# Proiect_v67.net
KiCad netlist of a schematic drawn in EAGLE
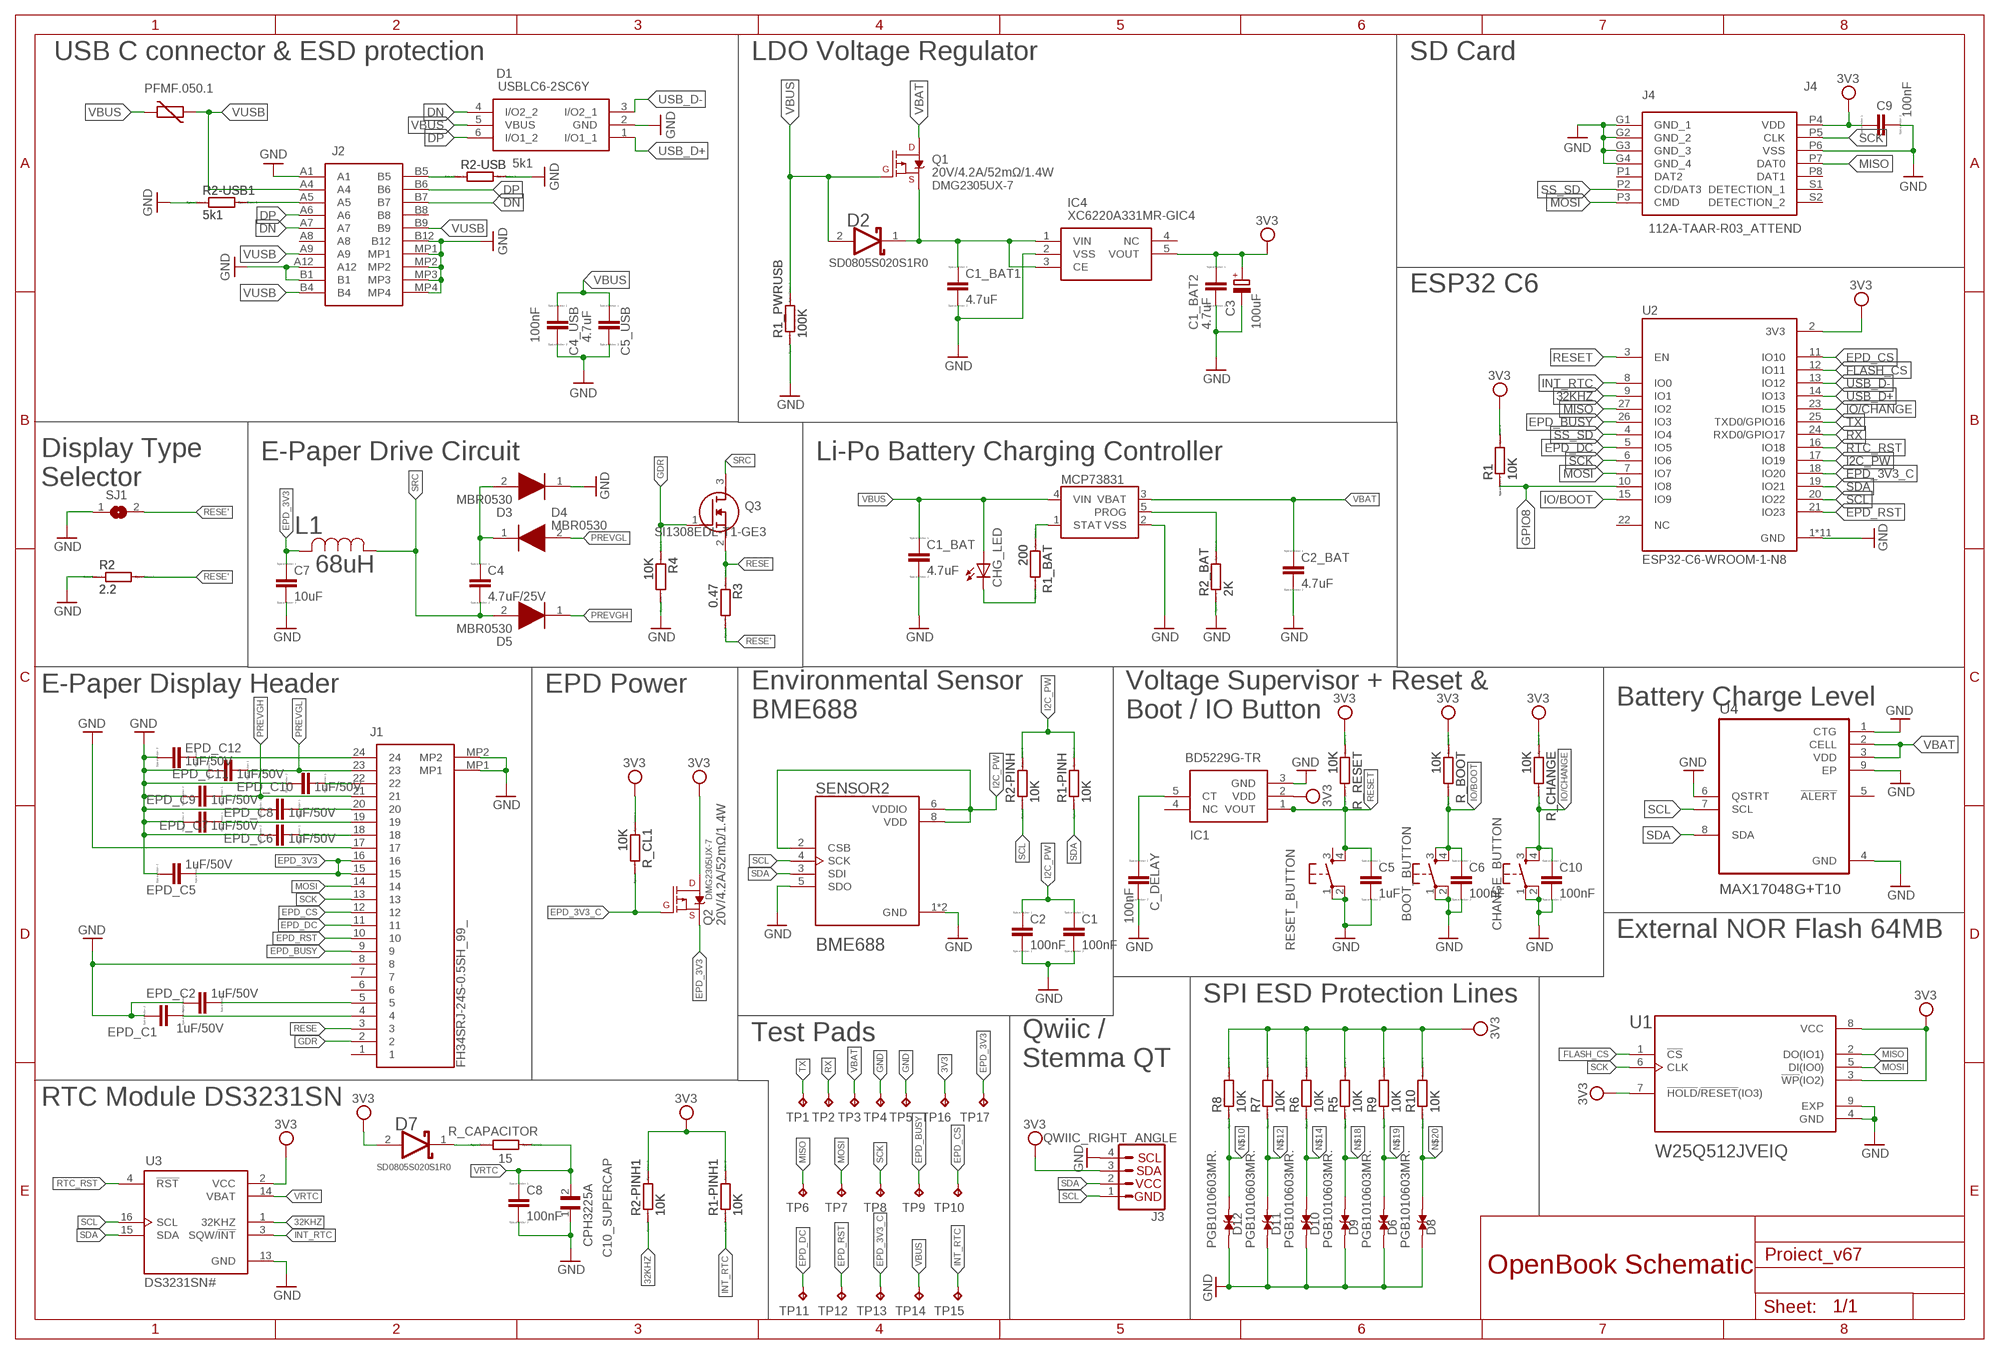
[diagram p0: schematic, sheet 1]

(export (version "E")
  (design (tool "Eeschema 10.0.6"))
  (components
    (comp (ref "BOOT_BUTTON")
      (value "BUTTON_CUSYOMV1.")
      (footprint "eagle-import:MYBUTTON")
      (libsource (lib "eagle-import") (part "BUTTON_CUSYOMV1."))
    )
    (comp (ref "C1")
      (value "100nF")
      (footprint "eagle-import:EAGLE-LTSPICE_C0402")
      (libsource (lib "eagle-import") (part "EAGLE-LTSPICE_C"))
    )
    (comp (ref "C1_BAT")
      (value "4.7uF")
      (footprint "eagle-import:EAGLE-LTSPICE_C0402")
      (libsource (lib "eagle-import") (part "EAGLE-LTSPICE_C"))
    )
    (comp (ref "C1_BAT1")
      (value "4.7uF")
      (footprint "eagle-import:EAGLE-LTSPICE_C0402")
      (libsource (lib "eagle-import") (part "EAGLE-LTSPICE_C"))
    )
    (comp (ref "C1_BAT2")
      (value "4.7uF")
      (footprint "eagle-import:EAGLE-LTSPICE_C0402")
      (libsource (lib "eagle-import") (part "EAGLE-LTSPICE_C"))
    )
    (comp (ref "C2")
      (value "100nF")
      (footprint "eagle-import:EAGLE-LTSPICE_C0402")
      (libsource (lib "eagle-import") (part "EAGLE-LTSPICE_C"))
    )
    (comp (ref "C2_BAT")
      (value "4.7uF")
      (footprint "eagle-import:EAGLE-LTSPICE_C0402")
      (libsource (lib "eagle-import") (part "EAGLE-LTSPICE_C"))
    )
    (comp (ref "C3")
      (value "100uF")
      (footprint "eagle-import:RCL_CT3528")
      (libsource (lib "eagle-import") (part "RCL_CPOL-EUCT3528"))
    )
    (comp (ref "C4")
      (value "4.7uF/25V")
      (footprint "eagle-import:EAGLE-LTSPICE_C0402")
      (libsource (lib "eagle-import") (part "EAGLE-LTSPICE_C"))
    )
    (comp (ref "C4_USB")
      (value "100nF")
      (footprint "eagle-import:EAGLE-LTSPICE_C0402")
      (libsource (lib "eagle-import") (part "EAGLE-LTSPICE_C"))
    )
    (comp (ref "C5")
      (value "1uF")
      (footprint "eagle-import:EAGLE-LTSPICE_C0402")
      (libsource (lib "eagle-import") (part "EAGLE-LTSPICE_C"))
    )
    (comp (ref "C5_USB")
      (value "4.7uF")
      (footprint "eagle-import:EAGLE-LTSPICE_C0402")
      (libsource (lib "eagle-import") (part "EAGLE-LTSPICE_C"))
    )
    (comp (ref "C6")
      (value "100nF")
      (footprint "eagle-import:EAGLE-LTSPICE_C0402")
      (libsource (lib "eagle-import") (part "EAGLE-LTSPICE_C"))
    )
    (comp (ref "C7")
      (value "10uF")
      (footprint "eagle-import:EAGLE-LTSPICE_C0402")
      (libsource (lib "eagle-import") (part "EAGLE-LTSPICE_C"))
    )
    (comp (ref "C8")
      (value "100nF")
      (footprint "eagle-import:EAGLE-LTSPICE_C0402")
      (libsource (lib "eagle-import") (part "EAGLE-LTSPICE_C"))
    )
    (comp (ref "C9")
      (value "100nF")
      (footprint "eagle-import:EAGLE-LTSPICE_C0402")
      (libsource (lib "eagle-import") (part "EAGLE-LTSPICE_C"))
    )
    (comp (ref "C10")
      (value "100nF")
      (footprint "eagle-import:EAGLE-LTSPICE_C0402")
      (libsource (lib "eagle-import") (part "EAGLE-LTSPICE_C"))
    )
    (comp (ref "C10_SUPERCAP")
      (value "CPH3225A")
      (footprint "eagle-import:CAPCP3225X100N")
      (fields (field (name "MF") "Seiko Instruments"))
      (libsource (lib "eagle-import") (part "CPH3225A"))
    )
    (comp (ref "CHANGE_BUTTON")
      (value "BUTTON_CUSYOMV1.")
      (footprint "eagle-import:MYBUTTON")
      (libsource (lib "eagle-import") (part "BUTTON_CUSYOMV1."))
    )
    (comp (ref "CHG_LED")
      (value "ADAFRUIT_LEDCHIP-LED0603")
      (footprint "eagle-import:ADAFRUIT_CHIP-LED0603")
      (libsource (lib "eagle-import") (part "ADAFRUIT_LEDCHIP-LED0603"))
    )
    (comp (ref "C_DELAY")
      (value "100nF")
      (footprint "eagle-import:EAGLE-LTSPICE_C0402")
      (libsource (lib "eagle-import") (part "EAGLE-LTSPICE_C"))
    )
    (comp (ref "D1")
      (value "USBLC6-2SC6Y")
      (footprint "eagle-import:SOT95P280X145-6N")
      (fields (field (name "MF") "STMicroelectronics"))
      (libsource (lib "eagle-import") (part "USBLC6-2SC6Y"))
    )
    (comp (ref "D2")
      (value "ESP32_WROVER_AVX---SD0805S020S1R0_AVX_SD0805S020S1R0_0_0AVX_SD0805S020S1R0_0_0")
      (footprint "eagle-import:ESP32_WROVER_AVX---SD0805S020S1R0_AVX_SD0805S020S1R0_0")
      (fields
        (field (name "DIGIKEY_PART_NUMBER") "478-7800-1-ND")
        (field (name "MF") "AVX")
        (field (name "MOUSER_PART_NUMBER") "581-SD0805S020S1R0")
        (field (name "ATR") "SD0805S020S1R0")
      )
      (libsource (lib "eagle-import") (part "ESP32_WROVER_AVX---SD0805S020S1R0_AVX_SD0805S020S1R0_0_0AVX_SD0805S020S1R0_0_0"))
    )
    (comp (ref "D3")
      (value "MBR0530")
      (footprint "eagle-import:SOD3716X135N")
      (fields (field (name "MF") "ON Semiconductor"))
      (libsource (lib "eagle-import") (part "MBR0530"))
    )
    (comp (ref "D4")
      (value "MBR0530")
      (footprint "eagle-import:SOD3716X135N")
      (fields (field (name "MF") "ON Semiconductor"))
      (libsource (lib "eagle-import") (part "MBR0530"))
    )
    (comp (ref "D5")
      (value "MBR0530")
      (footprint "eagle-import:SOD3716X135N")
      (fields (field (name "MF") "ON Semiconductor"))
      (libsource (lib "eagle-import") (part "MBR0530"))
    )
    (comp (ref "D6")
      (value "PGB1010603MR.")
      (footprint "eagle-import:DIOC1608X36N")
      (libsource (lib "eagle-import") (part "PGB1010603MR."))
    )
    (comp (ref "D7")
      (value "ESP32_WROVER_AVX---SD0805S020S1R0_AVX_SD0805S020S1R0_0_0AVX_SD0805S020S1R0_0_0")
      (footprint "eagle-import:ESP32_WROVER_AVX---SD0805S020S1R0_AVX_SD0805S020S1R0_0")
      (fields
        (field (name "DIGIKEY_PART_NUMBER") "478-7800-1-ND")
        (field (name "MF") "AVX")
        (field (name "MOUSER_PART_NUMBER") "581-SD0805S020S1R0")
        (field (name "ATR") "SD0805S020S1R0")
      )
      (libsource (lib "eagle-import") (part "ESP32_WROVER_AVX---SD0805S020S1R0_AVX_SD0805S020S1R0_0_0AVX_SD0805S020S1R0_0_0"))
    )
    (comp (ref "D8")
      (value "PGB1010603MR.")
      (footprint "eagle-import:DIOC1608X36N")
      (libsource (lib "eagle-import") (part "PGB1010603MR."))
    )
    (comp (ref "D9")
      (value "PGB1010603MR.")
      (footprint "eagle-import:DIOC1608X36N")
      (libsource (lib "eagle-import") (part "PGB1010603MR."))
    )
    (comp (ref "D10")
      (value "PGB1010603MR.")
      (footprint "eagle-import:DIOC1608X36N")
      (libsource (lib "eagle-import") (part "PGB1010603MR."))
    )
    (comp (ref "D11")
      (value "PGB1010603MR.")
      (footprint "eagle-import:DIOC1608X36N")
      (libsource (lib "eagle-import") (part "PGB1010603MR."))
    )
    (comp (ref "D12")
      (value "PGB1010603MR.")
      (footprint "eagle-import:DIOC1608X36N")
      (libsource (lib "eagle-import") (part "PGB1010603MR."))
    )
    (comp (ref "EPD_C1")
      (value "1uF/50V")
      (footprint "eagle-import:EAGLE-LTSPICE_C0402")
      (libsource (lib "eagle-import") (part "EAGLE-LTSPICE_C"))
    )
    (comp (ref "EPD_C2")
      (value "1uF/50V")
      (footprint "eagle-import:EAGLE-LTSPICE_C0402")
      (libsource (lib "eagle-import") (part "EAGLE-LTSPICE_C"))
    )
    (comp (ref "EPD_C5")
      (value "1uF/50V")
      (footprint "eagle-import:EAGLE-LTSPICE_C0402")
      (libsource (lib "eagle-import") (part "EAGLE-LTSPICE_C"))
    )
    (comp (ref "EPD_C6")
      (value "1uF/50V")
      (footprint "eagle-import:EAGLE-LTSPICE_C0402")
      (libsource (lib "eagle-import") (part "EAGLE-LTSPICE_C"))
    )
    (comp (ref "EPD_C7")
      (value "1uF/50V")
      (footprint "eagle-import:EAGLE-LTSPICE_C0402")
      (libsource (lib "eagle-import") (part "EAGLE-LTSPICE_C"))
    )
    (comp (ref "EPD_C8")
      (value "1uF/50V")
      (footprint "eagle-import:EAGLE-LTSPICE_C0402")
      (libsource (lib "eagle-import") (part "EAGLE-LTSPICE_C"))
    )
    (comp (ref "EPD_C9")
      (value "1uF/50V")
      (footprint "eagle-import:EAGLE-LTSPICE_C0402")
      (libsource (lib "eagle-import") (part "EAGLE-LTSPICE_C"))
    )
    (comp (ref "EPD_C10")
      (value "1uF/50V")
      (footprint "eagle-import:EAGLE-LTSPICE_C0402")
      (libsource (lib "eagle-import") (part "EAGLE-LTSPICE_C"))
    )
    (comp (ref "EPD_C11")
      (value "1uF/50V")
      (footprint "eagle-import:EAGLE-LTSPICE_C0402")
      (libsource (lib "eagle-import") (part "EAGLE-LTSPICE_C"))
    )
    (comp (ref "EPD_C12")
      (value "1uF/50V")
      (footprint "eagle-import:EAGLE-LTSPICE_C0402")
      (libsource (lib "eagle-import") (part "EAGLE-LTSPICE_C"))
    )
    (comp (ref "IC1")
      (value "BD5229G-TR")
      (footprint "eagle-import:SOT95P280X125-5N")
      (fields (field (name "MOUSER_PART_NUMBER") "755-BD5229G-TR"))
      (libsource (lib "eagle-import") (part "BD5229G-TR"))
    )
    (comp (ref "IC4")
      (value "XC6220A331MR-GIC4")
      (footprint "eagle-import:SOT95P280X120-5N")
      (libsource (lib "eagle-import") (part "XC6220A331MR-GIC4"))
    )
    (comp (ref "J1")
      (value "FH34SRJ-24S-0.5SH_99_")
      (footprint "eagle-import:FH34SRJ24S05SH99")
      (fields
        (field (name "MANUFACTURER_PART_NUMBER") "FH34SRJ-24S-0.5SH(99)")
        (field (name "MOUSER_PART_NUMBER") "798-FH34SRJ24S05SH99")
      )
      (libsource (lib "eagle-import") (part "FH34SRJ-24S-0.5SH_99_"))
    )
    (comp (ref "J2")
      (value "SAMACSYS_PARTS_USB4110-GF-A")
      (footprint "eagle-import:SAMACSYS_PARTS_USB4110GFA")
      (fields
        (field (name "MANUFACTURER_PART_NUMBER") "USB4110-GF-A")
        (field (name "MOUSER_PART_NUMBER") "640-USB4110-GF-A")
      )
      (libsource (lib "eagle-import") (part "SAMACSYS_PARTS_USB4110-GF-A"))
    )
    (comp (ref "J3")
      (value "QWIIC_RIGHT_ANGLE")
      (footprint "eagle-import:JST04_1MM_RA")
      (libsource (lib "eagle-import") (part "QWIIC_CONNECTORJS-1MM"))
    )
    (comp (ref "J4")
      (value "112A-TAAR-R03_ATTEND")
      (footprint "eagle-import:112ATAARR03ATTEND")
      (fields (field (name "MANUFACTURER_PART_NUMBER") "112A-TAAR-R03 ATTEND"))
      (libsource (lib "eagle-import") (part "112A-TAAR-R03_ATTEND"))
    )
    (comp (ref "L1")
      (value "68uH")
      (footprint "eagle-import:IND_4828-WE-TPC_WRE")
      (fields
        (field (name "MANUFACTURER_PART_NUMBER") "744043680")
        (field (name "COPYRIGHT") "Copyright (C) 2024 Ultra Librarian. All rights reserved.")
      )
      (libsource (lib "eagle-import") (part "744043680IND_4828-WE-TPC_WRE"))
    )
    (comp (ref "MCP73831")
      (value "ESP32_WROVER_SPARKFUN-IC-POWER_MCP73831")
      (footprint "eagle-import:ESP32_WROVER_SPARKFUN-IC-POWER_SOT23-5")
      (libsource (lib "eagle-import") (part "ESP32_WROVER_SPARKFUN-IC-POWER_MCP73831"))
    )
    (comp (ref "PFMF.050.1")
      (value "ESP32C6_VARISTORCN1812")
      (footprint "eagle-import:ESP32C6_VARISTOR_CT_CN1812")
      (libsource (lib "eagle-import") (part "ESP32C6_VARISTORCN1812"))
    )
    (comp (ref "Q1")
      (value "20V/4.2A/52mΩ/1.4W")
      (footprint "eagle-import:ESP32_WROVER_SPARKFUN-DISCRETESEMI_SOT23-3")
      (fields (field (name "ATR") "DMG2305UX-7"))
      (libsource (lib "eagle-import") (part "ESP32_WROVER_SPARKFUN-DISCRETESEMI_MOSFET_PCH-DMG2305UX-7"))
    )
    (comp (ref "Q2")
      (value "20V/4.2A/52mΩ/1.4W")
      (footprint "eagle-import:ESP32_WROVER_SPARKFUN-DISCRETESEMI_SOT23-3")
      (fields (field (name "ATR") "DMG2305UX-7"))
      (libsource (lib "eagle-import") (part "ESP32_WROVER_SPARKFUN-DISCRETESEMI_MOSFET_PCH-DMG2305UX-7"))
    )
    (comp (ref "Q3")
      (value "SI1308EDL-T1-GE3")
      (footprint "eagle-import:SOT65P210X110-3N")
      (fields (field (name "MF") "Vishay Siliconix"))
      (libsource (lib "eagle-import") (part "SI1308EDL-T1-GE3"))
    )
    (comp (ref "R1")
      (value "10K")
      (footprint "eagle-import:ESP32_WROVER_EAGLE-LTSPICE_R0402")
      (libsource (lib "eagle-import") (part "ESP32_WROVER_EAGLE-LTSPICE_RR0402"))
    )
    (comp (ref "R1-PINH")
      (value "10K")
      (footprint "eagle-import:ESP32_WROVER_EAGLE-LTSPICE_R0402")
      (libsource (lib "eagle-import") (part "ESP32_WROVER_EAGLE-LTSPICE_RR0402"))
    )
    (comp (ref "R1-PINH1")
      (value "10K")
      (footprint "eagle-import:ESP32_WROVER_EAGLE-LTSPICE_R0402")
      (libsource (lib "eagle-import") (part "ESP32_WROVER_EAGLE-LTSPICE_RR0402"))
    )
    (comp (ref "R1_BAT")
      (value "200")
      (footprint "eagle-import:ESP32_WROVER_EAGLE-LTSPICE_R0402")
      (libsource (lib "eagle-import") (part "ESP32_WROVER_EAGLE-LTSPICE_RR0402"))
    )
    (comp (ref "R1_PWRUSB")
      (value "100K")
      (footprint "eagle-import:ESP32_WROVER_EAGLE-LTSPICE_R0402")
      (libsource (lib "eagle-import") (part "ESP32_WROVER_EAGLE-LTSPICE_RR0402"))
    )
    (comp (ref "R2")
      (value "2.2")
      (footprint "eagle-import:ESP32_WROVER_EAGLE-LTSPICE_R0402")
      (libsource (lib "eagle-import") (part "ESP32_WROVER_EAGLE-LTSPICE_RR0402"))
    )
    (comp (ref "R2-PINH")
      (value "10K")
      (footprint "eagle-import:ESP32_WROVER_EAGLE-LTSPICE_R0402")
      (libsource (lib "eagle-import") (part "ESP32_WROVER_EAGLE-LTSPICE_RR0402"))
    )
    (comp (ref "R2-PINH1")
      (value "10K")
      (footprint "eagle-import:ESP32_WROVER_EAGLE-LTSPICE_R0402")
      (libsource (lib "eagle-import") (part "ESP32_WROVER_EAGLE-LTSPICE_RR0402"))
    )
    (comp (ref "R2-USB")
      (value "5k1")
      (footprint "eagle-import:ESP32_WROVER_EAGLE-LTSPICE_R0402")
      (libsource (lib "eagle-import") (part "ESP32_WROVER_EAGLE-LTSPICE_RR0402"))
    )
    (comp (ref "R2-USB1")
      (value "5k1")
      (footprint "eagle-import:ESP32_WROVER_EAGLE-LTSPICE_R0402")
      (libsource (lib "eagle-import") (part "ESP32_WROVER_EAGLE-LTSPICE_RR0402"))
    )
    (comp (ref "R2_BAT")
      (value "2K")
      (footprint "eagle-import:ESP32_WROVER_EAGLE-LTSPICE_R0402")
      (libsource (lib "eagle-import") (part "ESP32_WROVER_EAGLE-LTSPICE_RR0402"))
    )
    (comp (ref "R3")
      (value "0.47")
      (footprint "eagle-import:ESP32_WROVER_EAGLE-LTSPICE_R0402")
      (libsource (lib "eagle-import") (part "ESP32_WROVER_EAGLE-LTSPICE_RR0402"))
    )
    (comp (ref "R4")
      (value "10K")
      (footprint "eagle-import:ESP32_WROVER_EAGLE-LTSPICE_R0402")
      (libsource (lib "eagle-import") (part "ESP32_WROVER_EAGLE-LTSPICE_RR0402"))
    )
    (comp (ref "R5")
      (value "10K")
      (footprint "eagle-import:ESP32_WROVER_EAGLE-LTSPICE_R0402")
      (libsource (lib "eagle-import") (part "ESP32_WROVER_EAGLE-LTSPICE_RR0402"))
    )
    (comp (ref "R6")
      (value "10K")
      (footprint "eagle-import:ESP32_WROVER_EAGLE-LTSPICE_R0402")
      (libsource (lib "eagle-import") (part "ESP32_WROVER_EAGLE-LTSPICE_RR0402"))
    )
    (comp (ref "R7")
      (value "10K")
      (footprint "eagle-import:ESP32_WROVER_EAGLE-LTSPICE_R0402")
      (libsource (lib "eagle-import") (part "ESP32_WROVER_EAGLE-LTSPICE_RR0402"))
    )
    (comp (ref "R8")
      (value "10K")
      (footprint "eagle-import:ESP32_WROVER_EAGLE-LTSPICE_R0402")
      (libsource (lib "eagle-import") (part "ESP32_WROVER_EAGLE-LTSPICE_RR0402"))
    )
    (comp (ref "R9")
      (value "10K")
      (footprint "eagle-import:ESP32_WROVER_EAGLE-LTSPICE_R0402")
      (libsource (lib "eagle-import") (part "ESP32_WROVER_EAGLE-LTSPICE_RR0402"))
    )
    (comp (ref "R10")
      (value "10K")
      (footprint "eagle-import:ESP32_WROVER_EAGLE-LTSPICE_R0402")
      (libsource (lib "eagle-import") (part "ESP32_WROVER_EAGLE-LTSPICE_RR0402"))
    )
    (comp (ref "RESET_BUTTON")
      (value "BUTTON_CUSYOMV1.")
      (footprint "eagle-import:MYBUTTON")
      (libsource (lib "eagle-import") (part "BUTTON_CUSYOMV1."))
    )
    (comp (ref "R_BOOT")
      (value "10K")
      (footprint "eagle-import:ESP32_WROVER_EAGLE-LTSPICE_R0402")
      (libsource (lib "eagle-import") (part "ESP32_WROVER_EAGLE-LTSPICE_RR0402"))
    )
    (comp (ref "R_CAPACITOR")
      (value "15")
      (footprint "eagle-import:ESP32_WROVER_EAGLE-LTSPICE_R0402")
      (libsource (lib "eagle-import") (part "ESP32_WROVER_EAGLE-LTSPICE_RR0402"))
    )
    (comp (ref "R_CHANGE")
      (value "10K")
      (footprint "eagle-import:ESP32_WROVER_EAGLE-LTSPICE_R0402")
      (libsource (lib "eagle-import") (part "ESP32_WROVER_EAGLE-LTSPICE_RR0402"))
    )
    (comp (ref "R_CL1")
      (value "10K")
      (footprint "eagle-import:ESP32_WROVER_EAGLE-LTSPICE_R0402")
      (libsource (lib "eagle-import") (part "ESP32_WROVER_EAGLE-LTSPICE_RR0402"))
    )
    (comp (ref "R_RESET")
      (value "10K")
      (footprint "eagle-import:ESP32_WROVER_EAGLE-LTSPICE_R0402")
      (libsource (lib "eagle-import") (part "ESP32_WROVER_EAGLE-LTSPICE_RR0402"))
    )
    (comp (ref "SENSOR2")
      (value "ESP32_WROVER_BME680_BME680")
      (footprint "eagle-import:ESP32_WROVER_BME680_PSON80P300X300X100-8N")
      (fields
        (field (name "MF") "Bosch Sensortec")
        (field (name "MP") "BME680")
        (field (name "ATR") "BME688")
      )
      (libsource (lib "eagle-import") (part "ESP32_WROVER_BME680_BME680"))
    )
    (comp (ref "SJ1") (value "SJ") (footprint "eagle-import:SJ") (libsource (lib "eagle-import") (part "SJ")))
    (comp (ref "TP1")
      (value "TPTP20R")
      (footprint "eagle-import:TP20R")
      (libsource (lib "eagle-import") (part "TPTP20R"))
    )
    (comp (ref "TP2")
      (value "TPTP20R")
      (footprint "eagle-import:TP20R")
      (libsource (lib "eagle-import") (part "TPTP20R"))
    )
    (comp (ref "TP3")
      (value "TPTP20R")
      (footprint "eagle-import:TP20R")
      (libsource (lib "eagle-import") (part "TPTP20R"))
    )
    (comp (ref "TP4")
      (value "TPTP20R")
      (footprint "eagle-import:TP20R")
      (libsource (lib "eagle-import") (part "TPTP20R"))
    )
    (comp (ref "TP5")
      (value "TPTP20R")
      (footprint "eagle-import:TP20R")
      (libsource (lib "eagle-import") (part "TPTP20R"))
    )
    (comp (ref "TP6")
      (value "TPTP20R")
      (footprint "eagle-import:TP20R")
      (libsource (lib "eagle-import") (part "TPTP20R"))
    )
    (comp (ref "TP7")
      (value "TPTP20R")
      (footprint "eagle-import:TP20R")
      (libsource (lib "eagle-import") (part "TPTP20R"))
    )
    (comp (ref "TP8")
      (value "TPTP20R")
      (footprint "eagle-import:TP20R")
      (libsource (lib "eagle-import") (part "TPTP20R"))
    )
    (comp (ref "TP9")
      (value "TPTP20R")
      (footprint "eagle-import:TP20R")
      (libsource (lib "eagle-import") (part "TPTP20R"))
    )
    (comp (ref "TP10")
      (value "TPTP20R")
      (footprint "eagle-import:TP20R")
      (libsource (lib "eagle-import") (part "TPTP20R"))
    )
    (comp (ref "TP11")
      (value "TPTP20R")
      (footprint "eagle-import:TP20R")
      (libsource (lib "eagle-import") (part "TPTP20R"))
    )
    (comp (ref "TP12")
      (value "TPTP20R")
      (footprint "eagle-import:TP20R")
      (libsource (lib "eagle-import") (part "TPTP20R"))
    )
    (comp (ref "TP13")
      (value "TPTP20R")
      (footprint "eagle-import:TP20R")
      (libsource (lib "eagle-import") (part "TPTP20R"))
    )
    (comp (ref "TP14")
      (value "TPTP20R")
      (footprint "eagle-import:TP20R")
      (libsource (lib "eagle-import") (part "TPTP20R"))
    )
    (comp (ref "TP15")
      (value "TPTP20R")
      (footprint "eagle-import:TP20R")
      (libsource (lib "eagle-import") (part "TPTP20R"))
    )
    (comp (ref "TP16")
      (value "TPTP20R")
      (footprint "eagle-import:TP20R")
      (libsource (lib "eagle-import") (part "TPTP20R"))
    )
    (comp (ref "TP17")
      (value "TPTP20R")
      (footprint "eagle-import:TP20R")
      (libsource (lib "eagle-import") (part "TPTP20R"))
    )
    (comp (ref "U1")
      (value "W25Q512JVEIQ")
      (footprint "eagle-import:SON127P600X800X80-9N")
      (fields (field (name "MF") "Winbond Electronics"))
      (libsource (lib "eagle-import") (part "W25Q512JVEIQ"))
    )
    (comp (ref "U2")
      (value "ESP32-C6-WROOM-1-N8")
      (footprint "eagle-import:XCVR_ESP32-C6-WROOM-1-N8")
      (fields (field (name "MF") "Espressif Systems"))
      (libsource (lib "eagle-import") (part "ESP32-C6-WROOM-1-N8"))
    )
    (comp (ref "U3")
      (value "DS3231SN#")
      (footprint "eagle-import:SOIC127P1032X265-16N")
      (fields (field (name "MF") "Analog Devices"))
      (libsource (lib "eagle-import") (part "DS3231SN#"))
    )
    (comp (ref "U4")
      (value "MAX17048G+T10")
      (footprint "eagle-import:SON50P200X200X80-9N")
      (fields (field (name "MF") "Analog Devices"))
      (libsource (lib "eagle-import") (part "MAX17048G+T10"))
    )
  )
  (nets
    (net (code "1") (name "3V3") (class "Default")
      (node (ref "C1_BAT2") (pin "1") (pinfunction "1_1") (pintype "passive"))
      (node (ref "C3") (pin "+") (pinfunction "+_+") (pintype "passive"))
      (node (ref "C9") (pin "1") (pinfunction "1_1") (pintype "passive"))
      (node (ref "D7") (pin "2") (pinfunction "ANODE_2") (pintype "bidirectional"))
      (node (ref "IC1") (pin "2") (pinfunction "VDD_2") (pintype "bidirectional"))
      (node (ref "IC4") (pin "5") (pinfunction "VOUT_5") (pintype "bidirectional"))
      (node (ref "J3") (pin "3") (pinfunction "3_3") (pintype "passive"))
      (node (ref "J4") (pin "P4") (pinfunction "VDD_P4") (pintype "bidirectional"))
      (node (ref "Q2") (pin "3") (pinfunction "D_3") (pintype "bidirectional"))
      (node (ref "R1") (pin "2") (pinfunction "2_2") (pintype "passive"))
      (node (ref "R1-PINH1") (pin "2") (pinfunction "2_2") (pintype "passive"))
      (node (ref "R10") (pin "2") (pinfunction "2_2") (pintype "passive"))
      (node (ref "R2-PINH1") (pin "2") (pinfunction "2_2") (pintype "passive"))
      (node (ref "R5") (pin "2") (pinfunction "2_2") (pintype "passive"))
      (node (ref "R6") (pin "2") (pinfunction "2_2") (pintype "passive"))
      (node (ref "R7") (pin "2") (pinfunction "2_2") (pintype "passive"))
      (node (ref "R8") (pin "2") (pinfunction "2_2") (pintype "passive"))
      (node (ref "R9") (pin "2") (pinfunction "2_2") (pintype "passive"))
      (node (ref "R_BOOT") (pin "1") (pinfunction "1_1") (pintype "passive"))
      (node (ref "R_CHANGE") (pin "1") (pinfunction "1_1") (pintype "passive"))
      (node (ref "R_CL1") (pin "1") (pinfunction "1_1") (pintype "passive"))
      (node (ref "R_RESET") (pin "1") (pinfunction "1_1") (pintype "passive"))
      (node (ref "TP16") (pin "TP") (pinfunction "TP_TP") (pintype "input"))
      (node (ref "U1") (pin "3") (pinfunction "~{WP}(IO2)_3") (pintype "bidirectional"))
      (node (ref "U1") (pin "7") (pinfunction "~{HOLD}/~{RESET}(IO3)_7") (pintype "bidirectional"))
      (node (ref "U1") (pin "8") (pinfunction "VCC_8") (pintype "power_in"))
      (node (ref "U2") (pin "2") (pinfunction "3V3_2") (pintype "power_in"))
      (node (ref "U3") (pin "2") (pinfunction "VCC_2") (pintype "power_in"))
    )
    (net (code "2") (name "32KHZ") (class "Default")
      (node (ref "R2-PINH1") (pin "1") (pinfunction "1_1") (pintype "passive"))
      (node (ref "U2") (pin "9") (pinfunction "IO1_9") (pintype "bidirectional"))
      (node (ref "U3") (pin "1") (pinfunction "32KHZ_1") (pintype "output"))
    )
    (net (code "3") (name "DN") (class "Default")
      (node (ref "D1") (pin "4") (pinfunction "I/O2_2_4") (pintype "bidirectional"))
      (node (ref "J2") (pin "A7") (pinfunction "A7_A7") (pintype "bidirectional"))
      (node (ref "J2") (pin "B7") (pinfunction "B7_B7") (pintype "bidirectional"))
    )
    (net (code "4") (name "DP") (class "Default")
      (node (ref "D1") (pin "6") (pinfunction "I/O1_2_6") (pintype "bidirectional"))
      (node (ref "J2") (pin "A6") (pinfunction "A6_A6") (pintype "bidirectional"))
      (node (ref "J2") (pin "B6") (pinfunction "B6_B6") (pintype "bidirectional"))
    )
    (net (code "5") (name "EPD_3V3") (class "Default")
      (node (ref "C7") (pin "1") (pinfunction "1_1") (pintype "passive"))
      (node (ref "EPD_C5") (pin "1") (pinfunction "1_1") (pintype "passive"))
      (node (ref "J1") (pin "15") (pinfunction "15_15") (pintype "bidirectional"))
      (node (ref "J1") (pin "16") (pinfunction "16_16") (pintype "bidirectional"))
      (node (ref "L1") (pin "2") (pinfunction "2_2") (pintype "passive"))
      (node (ref "Q2") (pin "2") (pinfunction "S_2") (pintype "bidirectional"))
      (node (ref "TP17") (pin "TP") (pinfunction "TP_TP") (pintype "input"))
    )
    (net (code "6") (name "EPD_3V3_C") (class "Default")
      (node (ref "Q2") (pin "1") (pinfunction "G_1") (pintype "bidirectional"))
      (node (ref "R_CL1") (pin "2") (pinfunction "2_2") (pintype "passive"))
      (node (ref "TP13") (pin "TP") (pinfunction "TP_TP") (pintype "input"))
      (node (ref "U2") (pin "18") (pinfunction "IO20_18") (pintype "bidirectional"))
    )
    (net (code "7") (name "EPD_BUSY") (class "Default")
      (node (ref "J1") (pin "9") (pinfunction "9_9") (pintype "bidirectional"))
      (node (ref "TP9") (pin "TP") (pinfunction "TP_TP") (pintype "input"))
      (node (ref "U2") (pin "26") (pinfunction "IO3_26") (pintype "bidirectional"))
    )
    (net (code "8") (name "EPD_CS") (class "Default")
      (node (ref "J1") (pin "12") (pinfunction "12_12") (pintype "bidirectional"))
      (node (ref "TP10") (pin "TP") (pinfunction "TP_TP") (pintype "input"))
      (node (ref "U2") (pin "11") (pinfunction "IO10_11") (pintype "bidirectional"))
    )
    (net (code "9") (name "EPD_DC") (class "Default")
      (node (ref "J1") (pin "11") (pinfunction "11_11") (pintype "bidirectional"))
      (node (ref "TP11") (pin "TP") (pinfunction "TP_TP") (pintype "input"))
      (node (ref "U2") (pin "5") (pinfunction "IO5_5") (pintype "bidirectional"))
    )
    (net (code "10") (name "EPD_RST") (class "Default")
      (node (ref "J1") (pin "10") (pinfunction "10_10") (pintype "bidirectional"))
      (node (ref "TP12") (pin "TP") (pinfunction "TP_TP") (pintype "input"))
      (node (ref "U2") (pin "21") (pinfunction "IO23_21") (pintype "bidirectional"))
    )
    (net (code "11") (name "FLASH_CS") (class "Default")
      (node (ref "U1") (pin "1") (pinfunction "~{CS}_1") (pintype "input"))
      (node (ref "U2") (pin "12") (pinfunction "IO11_12") (pintype "bidirectional"))
    )
    (net (code "12") (name "GDR") (class "Default")
      (node (ref "J1") (pin "2") (pinfunction "2_2") (pintype "bidirectional"))
      (node (ref "Q3") (pin "1") (pinfunction "G_1") (pintype "bidirectional"))
      (node (ref "R4") (pin "1") (pinfunction "1_1") (pintype "passive"))
    )
    (net (code "13") (name "GND") (class "Default")
      (node (ref "BOOT_BUTTON") (pin "1") (pinfunction "1_1") (pintype "passive"))
      (node (ref "BOOT_BUTTON") (pin "2") (pinfunction "2_2") (pintype "passive"))
      (node (ref "C1") (pin "2") (pinfunction "2_2") (pintype "passive"))
      (node (ref "C10") (pin "2") (pinfunction "2_2") (pintype "passive"))
      (node (ref "C10_SUPERCAP") (pin "1") (pinfunction "1_1") (pintype "passive"))
      (node (ref "C1_BAT") (pin "2") (pinfunction "2_2") (pintype "passive"))
      (node (ref "C1_BAT1") (pin "2") (pinfunction "2_2") (pintype "passive"))
      (node (ref "C1_BAT2") (pin "2") (pinfunction "2_2") (pintype "passive"))
      (node (ref "C2") (pin "2") (pinfunction "2_2") (pintype "passive"))
      (node (ref "C2_BAT") (pin "2") (pinfunction "2_2") (pintype "passive"))
      (node (ref "C3") (pin "-") (pinfunction "-_-") (pintype "passive"))
      (node (ref "C4_USB") (pin "2") (pinfunction "2_2") (pintype "passive"))
      (node (ref "C5") (pin "2") (pinfunction "2_2") (pintype "passive"))
      (node (ref "C5_USB") (pin "2") (pinfunction "2_2") (pintype "passive"))
      (node (ref "C6") (pin "2") (pinfunction "2_2") (pintype "passive"))
      (node (ref "C7") (pin "2") (pinfunction "2_2") (pintype "passive"))
      (node (ref "C8") (pin "2") (pinfunction "2_2") (pintype "passive"))
      (node (ref "C9") (pin "2") (pinfunction "2_2") (pintype "passive"))
      (node (ref "CHANGE_BUTTON") (pin "1") (pinfunction "1_1") (pintype "passive"))
      (node (ref "CHANGE_BUTTON") (pin "2") (pinfunction "2_2") (pintype "passive"))
      (node (ref "C_DELAY") (pin "2") (pinfunction "2_2") (pintype "passive"))
      (node (ref "D1") (pin "2") (pinfunction "GND_2") (pintype "bidirectional"))
      (node (ref "D10") (pin "1") (pinfunction "1_1") (pintype "passive"))
      (node (ref "D11") (pin "1") (pinfunction "1_1") (pintype "passive"))
      (node (ref "D12") (pin "1") (pinfunction "1_1") (pintype "passive"))
      (node (ref "D3") (pin "1") (pinfunction "K_1") (pintype "bidirectional"))
      (node (ref "D6") (pin "1") (pinfunction "1_1") (pintype "passive"))
      (node (ref "D8") (pin "1") (pinfunction "1_1") (pintype "passive"))
      (node (ref "D9") (pin "1") (pinfunction "1_1") (pintype "passive"))
      (node (ref "EPD_C1") (pin "2") (pinfunction "2_2") (pintype "passive"))
      (node (ref "EPD_C10") (pin "2") (pinfunction "2_2") (pintype "passive"))
      (node (ref "EPD_C11") (pin "2") (pinfunction "2_2") (pintype "passive"))
      (node (ref "EPD_C12") (pin "2") (pinfunction "2_2") (pintype "passive"))
      (node (ref "EPD_C2") (pin "2") (pinfunction "2_2") (pintype "passive"))
      (node (ref "EPD_C5") (pin "2") (pinfunction "2_2") (pintype "passive"))
      (node (ref "EPD_C6") (pin "2") (pinfunction "2_2") (pintype "passive"))
      (node (ref "EPD_C7") (pin "2") (pinfunction "2_2") (pintype "passive"))
      (node (ref "EPD_C8") (pin "2") (pinfunction "2_2") (pintype "passive"))
      (node (ref "EPD_C9") (pin "2") (pinfunction "2_2") (pintype "passive"))
      (node (ref "IC1") (pin "3") (pinfunction "GND_3") (pintype "bidirectional"))
      (node (ref "IC4") (pin "2") (pinfunction "VSS_2") (pintype "bidirectional"))
      (node (ref "J1") (pin "17") (pinfunction "17_17") (pintype "bidirectional"))
      (node (ref "J1") (pin "8") (pinfunction "8_8") (pintype "bidirectional"))
      (node (ref "J1") (pin "MP1") (pinfunction "MP1_MP1") (pintype "bidirectional"))
      (node (ref "J1") (pin "MP2") (pinfunction "MP2_MP2") (pintype "bidirectional"))
      (node (ref "J2") (pin "A1") (pinfunction "A1_A1") (pintype "bidirectional"))
      (node (ref "J2") (pin "A12") (pinfunction "A12_A12") (pintype "bidirectional"))
      (node (ref "J2") (pin "B1") (pinfunction "B1_B1") (pintype "bidirectional"))
      (node (ref "J2") (pin "B12") (pinfunction "B12_B12") (pintype "bidirectional"))
      (node (ref "J2") (pin "MP1") (pinfunction "MP1_MP1") (pintype "bidirectional"))
      (node (ref "J2") (pin "MP2") (pinfunction "MP2_MP2") (pintype "bidirectional"))
      (node (ref "J2") (pin "MP3") (pinfunction "MP3_MP3") (pintype "bidirectional"))
      (node (ref "J2") (pin "MP4") (pinfunction "MP4_MP4") (pintype "bidirectional"))
      (node (ref "J3") (pin "4") (pinfunction "4_4") (pintype "passive"))
      (node (ref "J4") (pin "G1") (pinfunction "GND_1_G1") (pintype "bidirectional"))
      (node (ref "J4") (pin "G2") (pinfunction "GND_2_G2") (pintype "bidirectional"))
      (node (ref "J4") (pin "G3") (pinfunction "GND_3_G3") (pintype "bidirectional"))
      (node (ref "J4") (pin "G4") (pinfunction "GND_4_G4") (pintype "bidirectional"))
      (node (ref "J4") (pin "P6") (pinfunction "VSS_P6") (pintype "bidirectional"))
      (node (ref "MCP73831") (pin "2") (pinfunction "VSS_2") (pintype "power_in"))
      (node (ref "R1_PWRUSB") (pin "1") (pinfunction "1_1") (pintype "passive"))
      (node (ref "R2") (pin "1") (pinfunction "1_1") (pintype "passive"))
      (node (ref "R2-USB") (pin "2") (pinfunction "2_2") (pintype "passive"))
      (node (ref "R2-USB1") (pin "1") (pinfunction "1_1") (pintype "passive"))
      (node (ref "R2_BAT") (pin "1") (pinfunction "1_1") (pintype "passive"))
      (node (ref "R4") (pin "2") (pinfunction "2_2") (pintype "passive"))
      (node (ref "RESET_BUTTON") (pin "1") (pinfunction "1_1") (pintype "passive"))
      (node (ref "RESET_BUTTON") (pin "2") (pinfunction "2_2") (pintype "passive"))
      (node (ref "SENSOR2") (pin "1") (pinfunction "GND_1") (pintype "power_in"))
      (node (ref "SENSOR2") (pin "5") (pinfunction "SDO_5") (pintype "bidirectional"))
      (node (ref "SENSOR2") (pin "7") (pinfunction "GND_7") (pintype "power_in"))
      (node (ref "SJ1") (pin "1") (pinfunction "1_1") (pintype "passive"))
      (node (ref "TP4") (pin "TP") (pinfunction "TP_TP") (pintype "input"))
      (node (ref "TP5") (pin "TP") (pinfunction "TP_TP") (pintype "input"))
      (node (ref "U1") (pin "4") (pinfunction "GND_4") (pintype "power_in"))
      (node (ref "U1") (pin "9") (pinfunction "EXP_9") (pintype "passive"))
      (node (ref "U2") (pin "1") (pinfunction "GND_1") (pintype "power_in"))
      (node (ref "U2") (pin "28") (pinfunction "GND_28") (pintype "power_in"))
      (node (ref "U2") (pin "29_1") (pinfunction "GND_29_1") (pintype "power_in"))
      (node (ref "U2") (pin "29_2") (pinfunction "GND_29_2") (pintype "power_in"))
      (node (ref "U2") (pin "29_3") (pinfunction "GND_29_3") (pintype "power_in"))
      (node (ref "U2") (pin "29_4") (pinfunction "GND_29_4") (pintype "power_in"))
      (node (ref "U2") (pin "29_5") (pinfunction "GND_29_5") (pintype "power_in"))
      (node (ref "U2") (pin "29_6") (pinfunction "GND_29_6") (pintype "power_in"))
      (node (ref "U2") (pin "29_7") (pinfunction "GND_29_7") (pintype "power_in"))
      (node (ref "U2") (pin "29_8") (pinfunction "GND_29_8") (pintype "power_in"))
      (node (ref "U2") (pin "29_9") (pinfunction "GND_29_9") (pintype "power_in"))
      (node (ref "U3") (pin "13") (pinfunction "GND_13") (pintype "power_in"))
      (node (ref "U4") (pin "1") (pinfunction "CTG_1") (pintype "power_in"))
      (node (ref "U4") (pin "4") (pinfunction "GND_4") (pintype "power_in"))
      (node (ref "U4") (pin "6") (pinfunction "QSTRT_6") (pintype "input"))
      (node (ref "U4") (pin "9") (pinfunction "EP_9") (pintype "power_in"))
    )
    (net (code "14") (name "GPIO8") (class "Default")
      (node (ref "R1") (pin "1") (pinfunction "1_1") (pintype "passive"))
      (node (ref "U2") (pin "10") (pinfunction "IO8_10") (pintype "bidirectional"))
    )
    (net (code "15") (name "I2C_PW") (class "Default")
      (node (ref "C1") (pin "1") (pinfunction "1_1") (pintype "passive"))
      (node (ref "C2") (pin "1") (pinfunction "1_1") (pintype "passive"))
      (node (ref "R1-PINH") (pin "2") (pinfunction "2_2") (pintype "passive"))
      (node (ref "R2-PINH") (pin "2") (pinfunction "2_2") (pintype "passive"))
      (node (ref "SENSOR2") (pin "2") (pinfunction "CSB_2") (pintype "input"))
      (node (ref "SENSOR2") (pin "6") (pinfunction "VDDIO_6") (pintype "power_in"))
      (node (ref "SENSOR2") (pin "8") (pinfunction "VDD_8") (pintype "power_in"))
      (node (ref "U2") (pin "17") (pinfunction "IO19_17") (pintype "bidirectional"))
    )
    (net (code "16") (name "INT_RTC") (class "Default")
      (node (ref "R1-PINH1") (pin "1") (pinfunction "1_1") (pintype "passive"))
      (node (ref "TP15") (pin "TP") (pinfunction "TP_TP") (pintype "input"))
      (node (ref "U2") (pin "8") (pinfunction "IO0_8") (pintype "bidirectional"))
      (node (ref "U3") (pin "3") (pinfunction "SQW/~{INT}_3") (pintype "output"))
    )
    (net (code "17") (name "IO{slash}BOOT") (class "Default")
      (node (ref "BOOT_BUTTON") (pin "3") (pinfunction "3_3") (pintype "passive"))
      (node (ref "BOOT_BUTTON") (pin "4") (pinfunction "4_4") (pintype "passive"))
      (node (ref "C6") (pin "1") (pinfunction "1_1") (pintype "passive"))
      (node (ref "R_BOOT") (pin "2") (pinfunction "2_2") (pintype "passive"))
      (node (ref "U2") (pin "15") (pinfunction "IO9_15") (pintype "bidirectional"))
    )
    (net (code "18") (name "IO{slash}CHANGE") (class "Default")
      (node (ref "C10") (pin "1") (pinfunction "1_1") (pintype "passive"))
      (node (ref "CHANGE_BUTTON") (pin "3") (pinfunction "3_3") (pintype "passive"))
      (node (ref "CHANGE_BUTTON") (pin "4") (pinfunction "4_4") (pintype "passive"))
      (node (ref "R_CHANGE") (pin "2") (pinfunction "2_2") (pintype "passive"))
      (node (ref "U2") (pin "23") (pinfunction "IO15_23") (pintype "bidirectional"))
    )
    (net (code "19") (name "MISO") (class "Default")
      (node (ref "J4") (pin "P7") (pinfunction "DAT0_P7") (pintype "bidirectional"))
      (node (ref "TP6") (pin "TP") (pinfunction "TP_TP") (pintype "input"))
      (node (ref "U1") (pin "2") (pinfunction "DO(IO1)_2") (pintype "bidirectional"))
      (node (ref "U2") (pin "27") (pinfunction "IO2_27") (pintype "bidirectional"))
    )
    (net (code "20") (name "MOSI") (class "Default")
      (node (ref "J1") (pin "14") (pinfunction "14_14") (pintype "bidirectional"))
      (node (ref "J4") (pin "P3") (pinfunction "CMD_P3") (pintype "bidirectional"))
      (node (ref "TP7") (pin "TP") (pinfunction "TP_TP") (pintype "input"))
      (node (ref "U1") (pin "5") (pinfunction "DI(IO0)_5") (pintype "bidirectional"))
      (node (ref "U2") (pin "7") (pinfunction "IO7_7") (pintype "bidirectional"))
    )
    (net (code "21") (name "N$10") (class "Default")
      (node (ref "D12") (pin "2") (pinfunction "2_2") (pintype "passive"))
      (node (ref "R8") (pin "1") (pinfunction "1_1") (pintype "passive"))
    )
    (net (code "22") (name "N$12") (class "Default")
      (node (ref "D11") (pin "2") (pinfunction "2_2") (pintype "passive"))
      (node (ref "R7") (pin "1") (pinfunction "1_1") (pintype "passive"))
    )
    (net (code "23") (name "N$14") (class "Default")
      (node (ref "D10") (pin "2") (pinfunction "2_2") (pintype "passive"))
      (node (ref "R6") (pin "1") (pinfunction "1_1") (pintype "passive"))
    )
    (net (code "24") (name "N$18") (class "Default")
      (node (ref "D9") (pin "2") (pinfunction "2_2") (pintype "passive"))
      (node (ref "R5") (pin "1") (pinfunction "1_1") (pintype "passive"))
    )
    (net (code "25") (name "N$19") (class "Default")
      (node (ref "D6") (pin "2") (pinfunction "2_2") (pintype "passive"))
      (node (ref "R9") (pin "1") (pinfunction "1_1") (pintype "passive"))
    )
    (net (code "26") (name "N$20") (class "Default")
      (node (ref "D8") (pin "2") (pinfunction "2_2") (pintype "passive"))
      (node (ref "R10") (pin "1") (pinfunction "1_1") (pintype "passive"))
    )
    (net (code "27") (name "Net-(CHG_LED-PadC)") (class "Default")
      (node (ref "CHG_LED") (pin "C") (pinfunction "C_C") (pintype "passive"))
      (node (ref "R1_BAT") (pin "2") (pinfunction "2_2") (pintype "passive"))
    )
    (net (code "28") (name "Net-(D2-CATHODE)") (class "Default")
      (node (ref "C1_BAT1") (pin "1") (pinfunction "1_1") (pintype "passive"))
      (node (ref "D2") (pin "1") (pinfunction "CATHODE_1") (pintype "bidirectional"))
      (node (ref "IC4") (pin "1") (pinfunction "VIN_1") (pintype "bidirectional"))
      (node (ref "IC4") (pin "3") (pinfunction "CE_3") (pintype "bidirectional"))
      (node (ref "Q1") (pin "2") (pinfunction "S_2") (pintype "bidirectional"))
    )
    (net (code "29") (name "Net-(D3-A)") (class "Default")
      (node (ref "C4") (pin "1") (pinfunction "1_1") (pintype "passive"))
      (node (ref "D3") (pin "2") (pinfunction "A_2") (pintype "bidirectional"))
      (node (ref "D4") (pin "1") (pinfunction "K_1") (pintype "bidirectional"))
    )
    (net (code "30") (name "Net-(D7-CATHODE)") (class "Default")
      (node (ref "D7") (pin "1") (pinfunction "CATHODE_1") (pintype "bidirectional"))
      (node (ref "R_CAPACITOR") (pin "2") (pinfunction "2_2") (pintype "passive"))
    )
    (net (code "31") (name "Net-(EPD_C1-Pad1)") (class "Default")
      (node (ref "EPD_C1") (pin "1") (pinfunction "1_1") (pintype "passive"))
      (node (ref "J1") (pin "4") (pinfunction "4_4") (pintype "bidirectional"))
    )
    (net (code "32") (name "Net-(EPD_C2-Pad1)") (class "Default")
      (node (ref "EPD_C2") (pin "1") (pinfunction "1_1") (pintype "passive"))
      (node (ref "J1") (pin "5") (pinfunction "5_5") (pintype "bidirectional"))
    )
    (net (code "33") (name "Net-(EPD_C6-Pad1)") (class "Default")
      (node (ref "EPD_C6") (pin "1") (pinfunction "1_1") (pintype "passive"))
      (node (ref "J1") (pin "18") (pinfunction "18_18") (pintype "bidirectional"))
    )
    (net (code "34") (name "Net-(EPD_C7-Pad1)") (class "Default")
      (node (ref "EPD_C7") (pin "1") (pinfunction "1_1") (pintype "passive"))
      (node (ref "J1") (pin "19") (pinfunction "19_19") (pintype "bidirectional"))
    )
    (net (code "35") (name "Net-(EPD_C8-Pad1)") (class "Default")
      (node (ref "EPD_C8") (pin "1") (pinfunction "1_1") (pintype "passive"))
      (node (ref "J1") (pin "20") (pinfunction "20_20") (pintype "bidirectional"))
    )
    (net (code "36") (name "Net-(EPD_C10-Pad1)") (class "Default")
      (node (ref "EPD_C10") (pin "1") (pinfunction "1_1") (pintype "passive"))
      (node (ref "J1") (pin "22") (pinfunction "22_22") (pintype "bidirectional"))
    )
    (net (code "37") (name "Net-(EPD_C12-Pad1)") (class "Default")
      (node (ref "EPD_C12") (pin "1") (pinfunction "1_1") (pintype "passive"))
      (node (ref "J1") (pin "24") (pinfunction "24_24") (pintype "bidirectional"))
    )
    (net (code "38") (name "Net-(IC1-CT)") (class "Default")
      (node (ref "C_DELAY") (pin "1") (pinfunction "1_1") (pintype "passive"))
      (node (ref "IC1") (pin "5") (pinfunction "CT_5") (pintype "bidirectional"))
    )
    (net (code "39") (name "Net-(J2-PadA5)") (class "Default")
      (node (ref "J2") (pin "A5") (pinfunction "A5_A5") (pintype "bidirectional"))
      (node (ref "R2-USB1") (pin "2") (pinfunction "2_2") (pintype "passive"))
    )
    (net (code "40") (name "Net-(J2-PadB5)") (class "Default")
      (node (ref "J2") (pin "B5") (pinfunction "B5_B5") (pintype "bidirectional"))
      (node (ref "R2-USB") (pin "1") (pinfunction "1_1") (pintype "passive"))
    )
    (net (code "41") (name "Net-(MCP73831-PROG)") (class "Default")
      (node (ref "MCP73831") (pin "5") (pinfunction "PROG_5") (pintype "input"))
      (node (ref "R2_BAT") (pin "2") (pinfunction "2_2") (pintype "passive"))
    )
    (net (code "42") (name "Net-(MCP73831-STAT)") (class "Default")
      (node (ref "MCP73831") (pin "1") (pinfunction "STAT_1") (pintype "output"))
      (node (ref "R1_BAT") (pin "1") (pinfunction "1_1") (pintype "passive"))
    )
    (net (code "43") (name "PREVGH") (class "Default")
      (node (ref "D5") (pin "1") (pinfunction "K_1") (pintype "bidirectional"))
      (node (ref "EPD_C9") (pin "1") (pinfunction "1_1") (pintype "passive"))
      (node (ref "J1") (pin "21") (pinfunction "21_21") (pintype "bidirectional"))
    )
    (net (code "44") (name "PREVGL") (class "Default")
      (node (ref "D4") (pin "2") (pinfunction "A_2") (pintype "bidirectional"))
      (node (ref "EPD_C11") (pin "1") (pinfunction "1_1") (pintype "passive"))
      (node (ref "J1") (pin "23") (pinfunction "23_23") (pintype "bidirectional"))
    )
    (net (code "45") (name "RESE") (class "Default")
      (node (ref "J1") (pin "3") (pinfunction "3_3") (pintype "bidirectional"))
      (node (ref "Q3") (pin "2") (pinfunction "S_2") (pintype "bidirectional"))
      (node (ref "R3") (pin "1") (pinfunction "1_1") (pintype "passive"))
    )
    (net (code "46") (name "RESE'") (class "Default")
      (node (ref "R2") (pin "2") (pinfunction "2_2") (pintype "passive"))
      (node (ref "R3") (pin "2") (pinfunction "2_2") (pintype "passive"))
      (node (ref "SJ1") (pin "2") (pinfunction "2_2") (pintype "passive"))
    )
    (net (code "47") (name "RESET") (class "Default")
      (node (ref "C5") (pin "1") (pinfunction "1_1") (pintype "passive"))
      (node (ref "IC1") (pin "1") (pinfunction "VOUT_1") (pintype "bidirectional"))
      (node (ref "RESET_BUTTON") (pin "4") (pinfunction "4_4") (pintype "passive"))
      (node (ref "R_RESET") (pin "2") (pinfunction "2_2") (pintype "passive"))
      (node (ref "U2") (pin "3") (pinfunction "EN_3") (pintype "input"))
    )
    (net (code "48") (name "RTC_RST") (class "Default")
      (node (ref "U2") (pin "16") (pinfunction "IO18_16") (pintype "bidirectional"))
      (node (ref "U3") (pin "4") (pinfunction "~{RST}_4") (pintype "input"))
    )
    (net (code "49") (name "RX") (class "Default")
      (node (ref "TP2") (pin "TP") (pinfunction "TP_TP") (pintype "input"))
      (node (ref "U2") (pin "24") (pinfunction "RXD0/GPIO17_24") (pintype "bidirectional"))
    )
    (net (code "50") (name "SCK") (class "Default")
      (node (ref "J1") (pin "13") (pinfunction "13_13") (pintype "bidirectional"))
      (node (ref "J4") (pin "P5") (pinfunction "CLK_P5") (pintype "bidirectional"))
      (node (ref "TP8") (pin "TP") (pinfunction "TP_TP") (pintype "input"))
      (node (ref "U1") (pin "6") (pinfunction "CLK_6") (pintype "input"))
      (node (ref "U2") (pin "6") (pinfunction "IO6_6") (pintype "bidirectional"))
    )
    (net (code "51") (name "SCL") (class "Default")
      (node (ref "J3") (pin "1") (pinfunction "1_1") (pintype "power_in"))
      (node (ref "R2-PINH") (pin "1") (pinfunction "1_1") (pintype "passive"))
      (node (ref "SENSOR2") (pin "4") (pinfunction "SCK_4") (pintype "input"))
      (node (ref "U2") (pin "20") (pinfunction "IO22_20") (pintype "bidirectional"))
      (node (ref "U3") (pin "16") (pinfunction "SCL_16") (pintype "input"))
      (node (ref "U4") (pin "7") (pinfunction "SCL_7") (pintype "input"))
    )
    (net (code "52") (name "SDA") (class "Default")
      (node (ref "J3") (pin "2") (pinfunction "2_2") (pintype "power_in"))
      (node (ref "R1-PINH") (pin "1") (pinfunction "1_1") (pintype "passive"))
      (node (ref "SENSOR2") (pin "3") (pinfunction "SDI_3") (pintype "bidirectional"))
      (node (ref "U2") (pin "19") (pinfunction "IO21_19") (pintype "bidirectional"))
      (node (ref "U3") (pin "15") (pinfunction "SDA_15") (pintype "bidirectional"))
      (node (ref "U4") (pin "8") (pinfunction "SDA_8") (pintype "bidirectional"))
    )
    (net (code "53") (name "SRC") (class "Default")
      (node (ref "C4") (pin "2") (pinfunction "2_2") (pintype "passive"))
      (node (ref "D5") (pin "2") (pinfunction "A_2") (pintype "bidirectional"))
      (node (ref "L1") (pin "1") (pinfunction "1_1") (pintype "passive"))
      (node (ref "Q3") (pin "3") (pinfunction "D_3") (pintype "bidirectional"))
    )
    (net (code "54") (name "SS_SD") (class "Default")
      (node (ref "J4") (pin "P2") (pinfunction "CD/DAT3_P2") (pintype "bidirectional"))
      (node (ref "U2") (pin "4") (pinfunction "IO4_4") (pintype "bidirectional"))
    )
    (net (code "55") (name "TX") (class "Default")
      (node (ref "TP1") (pin "TP") (pinfunction "TP_TP") (pintype "input"))
      (node (ref "U2") (pin "25") (pinfunction "TXD0/GPIO16_25") (pintype "bidirectional"))
    )
    (net (code "56") (name "USB_D+") (class "Default")
      (node (ref "D1") (pin "1") (pinfunction "I/O1_1_1") (pintype "bidirectional"))
      (node (ref "U2") (pin "14") (pinfunction "IO13_14") (pintype "bidirectional"))
    )
    (net (code "57") (name "USB_D-") (class "Default")
      (node (ref "D1") (pin "3") (pinfunction "I/O2_1_3") (pintype "bidirectional"))
      (node (ref "U2") (pin "13") (pinfunction "IO12_13") (pintype "bidirectional"))
    )
    (net (code "58") (name "VBAT") (class "Default")
      (node (ref "C2_BAT") (pin "1") (pinfunction "1_1") (pintype "passive"))
      (node (ref "MCP73831") (pin "3") (pinfunction "VBAT_3") (pintype "power_in"))
      (node (ref "Q1") (pin "3") (pinfunction "D_3") (pintype "bidirectional"))
      (node (ref "TP3") (pin "TP") (pinfunction "TP_TP") (pintype "input"))
      (node (ref "U4") (pin "2") (pinfunction "CELL_2") (pintype "power_in"))
      (node (ref "U4") (pin "3") (pinfunction "VDD_3") (pintype "power_in"))
    )
    (net (code "59") (name "VBUS") (class "Default")
      (node (ref "C1_BAT") (pin "1") (pinfunction "1_1") (pintype "passive"))
      (node (ref "C4_USB") (pin "1") (pinfunction "1_1") (pintype "passive"))
      (node (ref "C5_USB") (pin "1") (pinfunction "1_1") (pintype "passive"))
      (node (ref "CHG_LED") (pin "A") (pinfunction "A_A") (pintype "passive"))
      (node (ref "D1") (pin "5") (pinfunction "VBUS_5") (pintype "bidirectional"))
      (node (ref "D2") (pin "2") (pinfunction "ANODE_2") (pintype "bidirectional"))
      (node (ref "MCP73831") (pin "4") (pinfunction "VIN_4") (pintype "power_in"))
      (node (ref "PFMF.050.1") (pin "2") (pinfunction "2_2") (pintype "passive"))
      (node (ref "Q1") (pin "1") (pinfunction "G_1") (pintype "bidirectional"))
      (node (ref "R1_PWRUSB") (pin "2") (pinfunction "2_2") (pintype "passive"))
      (node (ref "TP14") (pin "TP") (pinfunction "TP_TP") (pintype "input"))
    )
    (net (code "60") (name "VRTC") (class "Default")
      (node (ref "C10_SUPERCAP") (pin "2") (pinfunction "2_2") (pintype "passive"))
      (node (ref "C8") (pin "1") (pinfunction "1_1") (pintype "passive"))
      (node (ref "R_CAPACITOR") (pin "1") (pinfunction "1_1") (pintype "passive"))
      (node (ref "U3") (pin "14") (pinfunction "VBAT_14") (pintype "power_in"))
    )
    (net (code "61") (name "VUSB") (class "Default")
      (node (ref "J2") (pin "A4") (pinfunction "A4_A4") (pintype "bidirectional"))
      (node (ref "J2") (pin "A9") (pinfunction "A9_A9") (pintype "bidirectional"))
      (node (ref "J2") (pin "B4") (pinfunction "B4_B4") (pintype "bidirectional"))
      (node (ref "J2") (pin "B9") (pinfunction "B9_B9") (pintype "bidirectional"))
      (node (ref "PFMF.050.1") (pin "1") (pinfunction "1_1") (pintype "passive"))
    )
    (net (code "62") (name "unconnected-(IC1-NC-Pad4)") (class "Default")
      (node (ref "IC1") (pin "4") (pinfunction "NC_4") (pintype "no_connect"))
    )
    (net (code "63") (name "unconnected-(IC4-NC-Pad4)") (class "Default")
      (node (ref "IC4") (pin "4") (pinfunction "NC_4") (pintype "no_connect"))
    )
    (net (code "64") (name "unconnected-(J1-Pad1)") (class "Default")
      (node (ref "J1") (pin "1") (pinfunction "1_1") (pintype "bidirectional"))
    )
    (net (code "65") (name "unconnected-(J1-Pad6)") (class "Default")
      (node (ref "J1") (pin "6") (pinfunction "6_6") (pintype "bidirectional"))
    )
    (net (code "66") (name "unconnected-(J1-Pad7)") (class "Default")
      (node (ref "J1") (pin "7") (pinfunction "7_7") (pintype "bidirectional"))
    )
    (net (code "67") (name "unconnected-(J2-PadA8)") (class "Default")
      (node (ref "J2") (pin "A8") (pinfunction "A8_A8") (pintype "bidirectional"))
    )
    (net (code "68") (name "unconnected-(J2-PadB8)") (class "Default")
      (node (ref "J2") (pin "B8") (pinfunction "B8_B8") (pintype "bidirectional"))
    )
    (net (code "69") (name "unconnected-(J4-DAT1-PadP8)") (class "Default")
      (node (ref "J4") (pin "P8") (pinfunction "DAT1_P8") (pintype "bidirectional"))
    )
    (net (code "70") (name "unconnected-(J4-DAT2-PadP1)") (class "Default")
      (node (ref "J4") (pin "P1") (pinfunction "DAT2_P1") (pintype "bidirectional"))
    )
    (net (code "71") (name "unconnected-(J4-DETECTION_1-PadS1)") (class "Default")
      (node (ref "J4") (pin "S1") (pinfunction "DETECTION_1_S1") (pintype "bidirectional"))
    )
    (net (code "72") (name "unconnected-(J4-DETECTION_2-PadS2)") (class "Default")
      (node (ref "J4") (pin "S2") (pinfunction "DETECTION_2_S2") (pintype "bidirectional"))
    )
    (net (code "73") (name "unconnected-(RESET_BUTTON-Pad3)") (class "Default")
      (node (ref "RESET_BUTTON") (pin "3") (pinfunction "3_3") (pintype "passive"))
    )
    (net (code "74") (name "unconnected-(U2-NC-Pad22)") (class "Default")
      (node (ref "U2") (pin "22") (pinfunction "NC_22") (pintype "no_connect"))
    )
    (net (code "75") (name "unconnected-(U4-~{ALERT}-Pad5)") (class "Default")
      (node (ref "U4") (pin "5") (pinfunction "~{ALERT}_5") (pintype "output"))
    )
  )
)
